# Temp_Sensirion_assy_FPC.net
KiCad netlist of a schematic drawn in Altium Designer
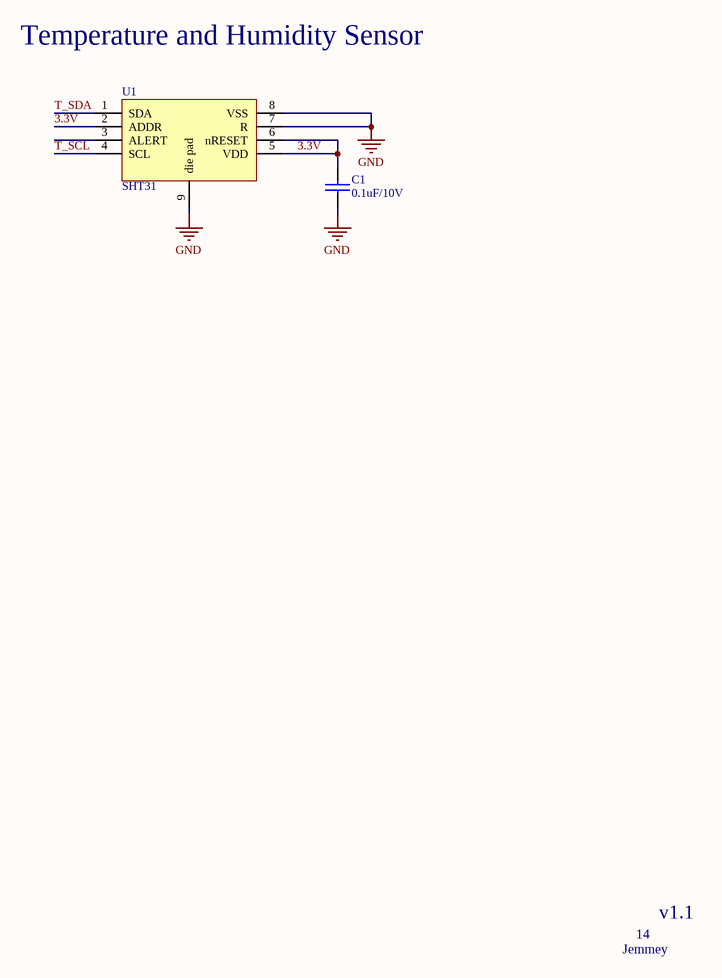
[diagram p0: Temp Sensirion assy FPC.SchDoc]

(export (version "E")
  (design (tool "Eeschema 10.0.6"))
  (components
    (comp (ref "C1")
      (value "0.1uF/10V")
      (footprint "0402C")
      (description "厂家：Murata，型号：GRM155R71A104KA01D")
      (libsource (lib "*") (part "CAP"))
    )
    (comp (ref "U1")
      (value "SHT31")
      (footprint "DFN")
      (description "厂家：盛思睿，型号：SHT31")
      (libsource (lib "Temp Sensirion assy FPC") (part "SHT31"))
    )
  )
  (nets
    (net (code "1") (name "/3.3V") (class "Default")
      (node (ref "C1") (pin "1") (pinfunction "1_1") (pintype "passive"))
      (node (ref "U1") (pin "2") (pinfunction "ADDR_2") (pintype "passive"))
      (node (ref "U1") (pin "5") (pinfunction "VDD_5") (pintype "passive"))
      (node (ref "U1") (pin "6") (pinfunction "nRESET_6") (pintype "passive"))
    )
    (net (code "2") (name "/T_SCL") (class "Default")
      (node (ref "U1") (pin "4") (pinfunction "SCL_4") (pintype "passive"))
    )
    (net (code "3") (name "/T_SDA") (class "Default")
      (node (ref "U1") (pin "1") (pinfunction "SDA_1") (pintype "passive"))
    )
    (net (code "4") (name "GND") (class "Default")
      (node (ref "C1") (pin "2") (pinfunction "2_2") (pintype "passive"))
      (node (ref "U1") (pin "7") (pinfunction "R_7") (pintype "passive"))
      (node (ref "U1") (pin "8") (pinfunction "VSS_8") (pintype "passive"))
      (node (ref "U1") (pin "9") (pinfunction "die_pad_9") (pintype "passive"))
    )
    (net (code "5") (name "unconnected-(U1-ALERT-Pad3)") (class "Default")
      (node (ref "U1") (pin "3") (pinfunction "ALERT_3") (pintype "passive"))
    )
  )
)
